# power_board_pcie.net
KiCad netlist of a schematic drawn in EAGLE
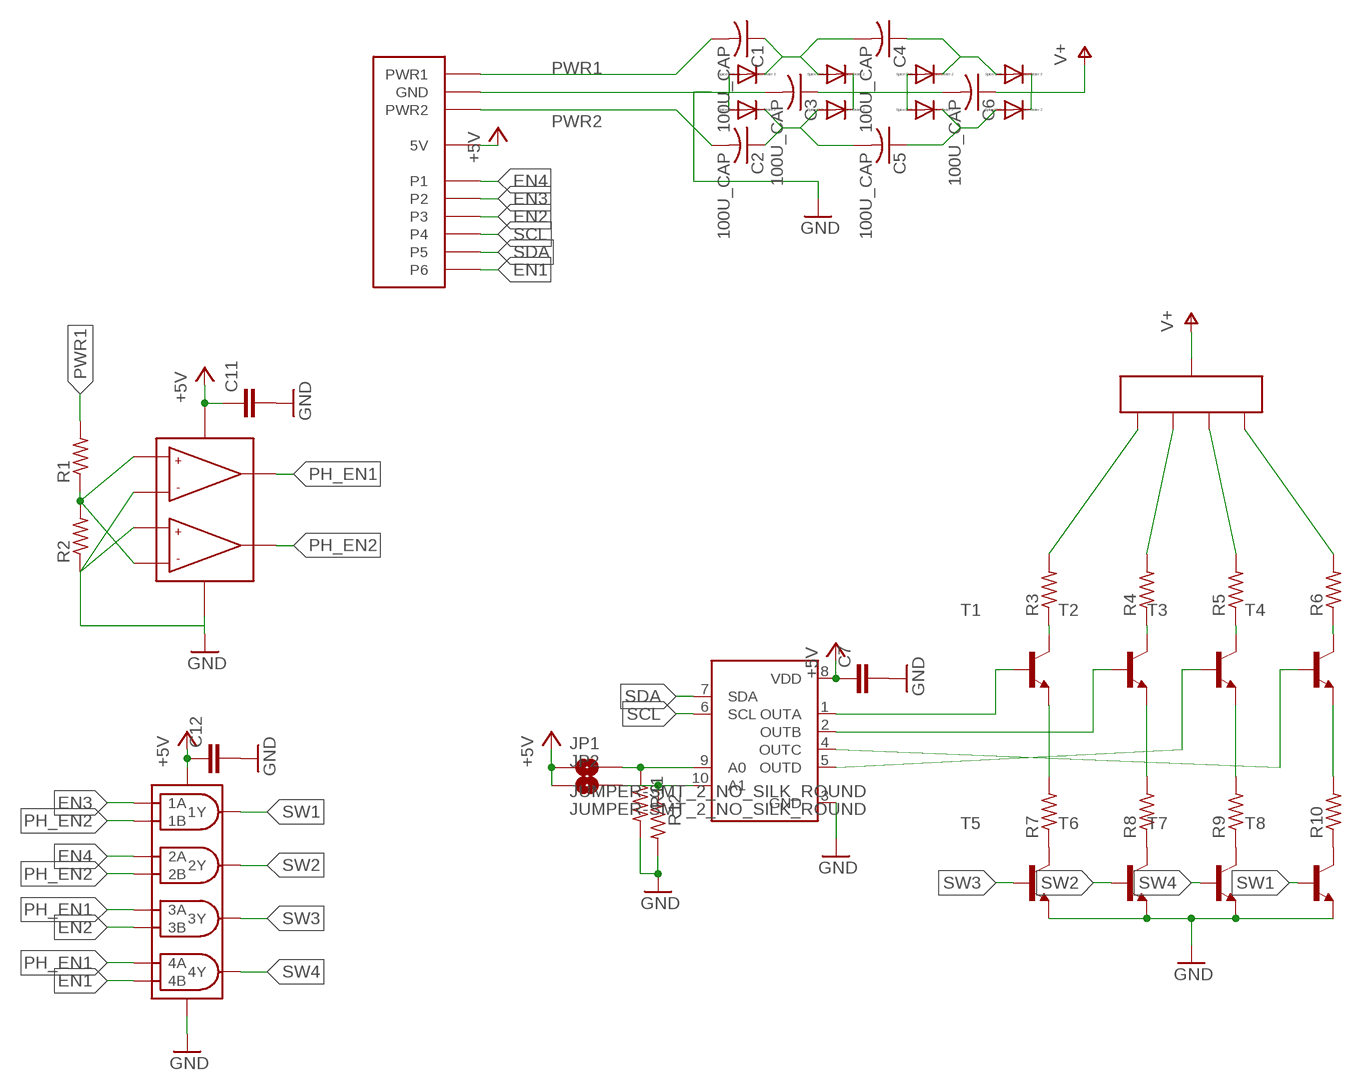
[diagram p0: schematic, sheet 1]

(export (version "E")
  (design (tool "Eeschema 10.0.6"))
  (components
    (comp (ref "C1")
      (value "100U_CAP")
      (footprint "eagle-import:100U_CAP")
      (libsource (lib "eagle-import") (part "100U_CAP"))
    )
    (comp (ref "C2")
      (value "100U_CAP")
      (footprint "eagle-import:100U_CAP")
      (libsource (lib "eagle-import") (part "100U_CAP"))
    )
    (comp (ref "C3")
      (value "100U_CAP")
      (footprint "eagle-import:100U_CAP")
      (libsource (lib "eagle-import") (part "100U_CAP"))
    )
    (comp (ref "C4")
      (value "100U_CAP")
      (footprint "eagle-import:100U_CAP")
      (libsource (lib "eagle-import") (part "100U_CAP"))
    )
    (comp (ref "C5")
      (value "100U_CAP")
      (footprint "eagle-import:100U_CAP")
      (libsource (lib "eagle-import") (part "100U_CAP"))
    )
    (comp (ref "C6")
      (value "100U_CAP")
      (footprint "eagle-import:100U_CAP")
      (libsource (lib "eagle-import") (part "100U_CAP"))
    )
    (comp (ref "C7")
      (value "C-EUC1206")
      (footprint "eagle-import:C1206")
      (libsource (lib "eagle-import") (part "C-EUC1206"))
    )
    (comp (ref "C11")
      (value "C-EUC1206")
      (footprint "eagle-import:C1206")
      (libsource (lib "eagle-import") (part "C-EUC1206"))
    )
    (comp (ref "C12")
      (value "C-EUC1206")
      (footprint "eagle-import:C1206")
      (libsource (lib "eagle-import") (part "C-EUC1206"))
    )
    (comp (ref "D1")
      (value "BAS16GW")
      (footprint "eagle-import:SOD3616X130")
      (libsource (lib "eagle-import") (part "BAS16GW"))
    )
    (comp (ref "D2")
      (value "BAS16GW")
      (footprint "eagle-import:SOD3616X130")
      (libsource (lib "eagle-import") (part "BAS16GW"))
    )
    (comp (ref "D3")
      (value "BAS16GW")
      (footprint "eagle-import:SOD3616X130")
      (libsource (lib "eagle-import") (part "BAS16GW"))
    )
    (comp (ref "D4")
      (value "BAS16GW")
      (footprint "eagle-import:SOD3616X130")
      (libsource (lib "eagle-import") (part "BAS16GW"))
    )
    (comp (ref "D5")
      (value "BAS16GW")
      (footprint "eagle-import:SOD3616X130")
      (libsource (lib "eagle-import") (part "BAS16GW"))
    )
    (comp (ref "D6")
      (value "BAS16GW")
      (footprint "eagle-import:SOD3616X130")
      (libsource (lib "eagle-import") (part "BAS16GW"))
    )
    (comp (ref "D7")
      (value "BAS16GW")
      (footprint "eagle-import:SOD3616X130")
      (libsource (lib "eagle-import") (part "BAS16GW"))
    )
    (comp (ref "D8")
      (value "BAS16GW")
      (footprint "eagle-import:SOD3616X130")
      (libsource (lib "eagle-import") (part "BAS16GW"))
    )
    (comp (ref "J1")
      (value "PCIE_EDGE")
      (footprint "eagle-import:PCIE_EDGE")
      (libsource (lib "eagle-import") (part "PCIE_EDGE"))
    )
    (comp (ref "JP1")
      (value "JUMPER-SMT_2_NO_SILK_ROUND")
      (footprint "eagle-import:SMT-JUMPER_2_NO_SILK_ROUND")
      (libsource (lib "eagle-import") (part "JUMPER-SMT_2_NO_SILK_ROUND"))
    )
    (comp (ref "JP2")
      (value "JUMPER-SMT_2_NO_SILK_ROUND")
      (footprint "eagle-import:SMT-JUMPER_2_NO_SILK_ROUND")
      (libsource (lib "eagle-import") (part "JUMPER-SMT_2_NO_SILK_ROUND"))
    )
    (comp (ref "R1")
      (value "R-US_R1206")
      (footprint "eagle-import:R1206")
      (libsource (lib "eagle-import") (part "R-US_R1206"))
    )
    (comp (ref "R2")
      (value "R-US_R1206")
      (footprint "eagle-import:R1206")
      (libsource (lib "eagle-import") (part "R-US_R1206"))
    )
    (comp (ref "R3")
      (value "R-US_R1206")
      (footprint "eagle-import:R1206")
      (libsource (lib "eagle-import") (part "R-US_R1206"))
    )
    (comp (ref "R4")
      (value "R-US_R1206")
      (footprint "eagle-import:R1206")
      (libsource (lib "eagle-import") (part "R-US_R1206"))
    )
    (comp (ref "R5")
      (value "R-US_R1206")
      (footprint "eagle-import:R1206")
      (libsource (lib "eagle-import") (part "R-US_R1206"))
    )
    (comp (ref "R6")
      (value "R-US_R1206")
      (footprint "eagle-import:R1206")
      (libsource (lib "eagle-import") (part "R-US_R1206"))
    )
    (comp (ref "R7")
      (value "R-US_R1206")
      (footprint "eagle-import:R1206")
      (libsource (lib "eagle-import") (part "R-US_R1206"))
    )
    (comp (ref "R8")
      (value "R-US_R1206")
      (footprint "eagle-import:R1206")
      (libsource (lib "eagle-import") (part "R-US_R1206"))
    )
    (comp (ref "R9")
      (value "R-US_R1206")
      (footprint "eagle-import:R1206")
      (libsource (lib "eagle-import") (part "R-US_R1206"))
    )
    (comp (ref "R10")
      (value "R-US_R1206")
      (footprint "eagle-import:R1206")
      (libsource (lib "eagle-import") (part "R-US_R1206"))
    )
    (comp (ref "R11")
      (value "R-US_R0603")
      (footprint "eagle-import:R0603")
      (libsource (lib "eagle-import") (part "R-US_R0603"))
    )
    (comp (ref "R12")
      (value "R-US_R0603")
      (footprint "eagle-import:R0603")
      (libsource (lib "eagle-import") (part "R-US_R0603"))
    )
    (comp (ref "T1")
      (value "-NPN-SOT23-EBC")
      (footprint "eagle-import:SOT23-EBC")
      (libsource (lib "eagle-import") (part "-NPN-SOT23-EBC"))
    )
    (comp (ref "T2")
      (value "-NPN-SOT23-EBC")
      (footprint "eagle-import:SOT23-EBC")
      (libsource (lib "eagle-import") (part "-NPN-SOT23-EBC"))
    )
    (comp (ref "T3")
      (value "-NPN-SOT23-EBC")
      (footprint "eagle-import:SOT23-EBC")
      (libsource (lib "eagle-import") (part "-NPN-SOT23-EBC"))
    )
    (comp (ref "T4")
      (value "-NPN-SOT23-EBC")
      (footprint "eagle-import:SOT23-EBC")
      (libsource (lib "eagle-import") (part "-NPN-SOT23-EBC"))
    )
    (comp (ref "T5")
      (value "-NPN-SOT23-EBC")
      (footprint "eagle-import:SOT23-EBC")
      (libsource (lib "eagle-import") (part "-NPN-SOT23-EBC"))
    )
    (comp (ref "T6")
      (value "-NPN-SOT23-EBC")
      (footprint "eagle-import:SOT23-EBC")
      (libsource (lib "eagle-import") (part "-NPN-SOT23-EBC"))
    )
    (comp (ref "T7")
      (value "-NPN-SOT23-EBC")
      (footprint "eagle-import:SOT23-EBC")
      (libsource (lib "eagle-import") (part "-NPN-SOT23-EBC"))
    )
    (comp (ref "T8")
      (value "-NPN-SOT23-EBC")
      (footprint "eagle-import:SOT23-EBC")
      (libsource (lib "eagle-import") (part "-NPN-SOT23-EBC"))
    )
    (comp (ref "U$3")
      (value "POWER_EDGE")
      (footprint "eagle-import:POWER_EDGE")
      (libsource (lib "eagle-import") (part "POWER_EDGE"))
    )
    (comp (ref "U1")
      (value "74HCT08D")
      (footprint "eagle-import:SOIC127P600X175-14")
      (libsource (lib "eagle-import") (part "74HCT08D"))
    )
    (comp (ref "U2")
      (value "DAC5574")
      (footprint "eagle-import:SOP50P490X110-10")
      (libsource (lib "eagle-import") (part "DAC5574"))
    )
    (comp (ref "U3")
      (value "AZ4558CMTR-G1")
      (footprint "eagle-import:SOIC127P600X175-8")
      (libsource (lib "eagle-import") (part "AZ4558CMTR-G1"))
    )
  )
  (nets
    (net (code "1") (name "+5V") (class "Default")
      (node (ref "C11") (pin "1") (pinfunction "1_1") (pintype "passive"))
      (node (ref "C12") (pin "1") (pinfunction "1_1") (pintype "passive"))
      (node (ref "C7") (pin "1") (pinfunction "1_1") (pintype "passive"))
      (node (ref "J1") (pin "PWR3") (pinfunction "5V_PWR3") (pintype "passive"))
      (node (ref "J1") (pin "PWR3_2") (pinfunction "5V_PWR3_2") (pintype "passive"))
      (node (ref "JP1") (pin "1") (pinfunction "1_1") (pintype "passive"))
      (node (ref "JP2") (pin "1") (pinfunction "1_1") (pintype "passive"))
      (node (ref "U1") (pin "14") (pinfunction "VCC_14") (pintype "passive"))
      (node (ref "U2") (pin "8") (pinfunction "VDD_8") (pintype "bidirectional"))
      (node (ref "U3") (pin "8") (pinfunction "VCC_8") (pintype "bidirectional"))
    )
    (net (code "2") (name "/PWR2") (class "Default")
      (node (ref "C2") (pin "C") (pinfunction "2_C") (pintype "passive"))
      (node (ref "J1") (pin "P$3") (pinfunction "PWR2_P$3") (pintype "passive"))
      (node (ref "J1") (pin "P$6") (pinfunction "PWR2_P$6") (pintype "passive"))
    )
    (net (code "3") (name "EN1") (class "Default")
      (node (ref "J1") (pin "P6") (pinfunction "P6_P6") (pintype "bidirectional"))
      (node (ref "U1") (pin "13") (pinfunction "4B_13") (pintype "input"))
    )
    (net (code "4") (name "EN2") (class "Default")
      (node (ref "J1") (pin "P3") (pinfunction "P3_P3") (pintype "bidirectional"))
      (node (ref "U1") (pin "10") (pinfunction "3B_10") (pintype "input"))
    )
    (net (code "5") (name "EN3") (class "Default")
      (node (ref "J1") (pin "P2") (pinfunction "P2_P2") (pintype "bidirectional"))
      (node (ref "U1") (pin "1") (pinfunction "1A_1") (pintype "input"))
    )
    (net (code "6") (name "EN4") (class "Default")
      (node (ref "J1") (pin "P1") (pinfunction "P1_P1") (pintype "bidirectional"))
      (node (ref "U1") (pin "4") (pinfunction "2A_4") (pintype "input"))
    )
    (net (code "7") (name "GND") (class "Default")
      (node (ref "C11") (pin "2") (pinfunction "2_2") (pintype "passive"))
      (node (ref "C12") (pin "2") (pinfunction "2_2") (pintype "passive"))
      (node (ref "C3") (pin "C") (pinfunction "2_C") (pintype "passive"))
      (node (ref "C7") (pin "2") (pinfunction "2_2") (pintype "passive"))
      (node (ref "D1") (pin "2") (pinfunction "A_2") (pintype "passive"))
      (node (ref "D2") (pin "2") (pinfunction "A_2") (pintype "passive"))
      (node (ref "J1") (pin "P$2") (pinfunction "GND_P$2") (pintype "passive"))
      (node (ref "J1") (pin "P$5") (pinfunction "GND_P$5") (pintype "passive"))
      (node (ref "R11") (pin "2") (pinfunction "2_2") (pintype "passive"))
      (node (ref "R12") (pin "2") (pinfunction "2_2") (pintype "passive"))
      (node (ref "R2") (pin "1") (pinfunction "1_1") (pintype "passive"))
      (node (ref "T5") (pin "E") (pinfunction "E_E") (pintype "passive"))
      (node (ref "T6") (pin "E") (pinfunction "E_E") (pintype "passive"))
      (node (ref "T7") (pin "E") (pinfunction "E_E") (pintype "passive"))
      (node (ref "T8") (pin "E") (pinfunction "E_E") (pintype "passive"))
      (node (ref "U1") (pin "7") (pinfunction "GND_7") (pintype "passive"))
      (node (ref "U2") (pin "3") (pinfunction "GND_3") (pintype "bidirectional"))
      (node (ref "U3") (pin "2") (pinfunction "IN1-_2") (pintype "input"))
      (node (ref "U3") (pin "4") (pinfunction "VEE_4") (pintype "bidirectional"))
      (node (ref "U3") (pin "5") (pinfunction "IN2+_5") (pintype "input"))
    )
    (net (code "8") (name "Net-(C1-1)") (class "Default")
      (node (ref "C1") (pin "A") (pinfunction "1_A") (pintype "passive"))
      (node (ref "C4") (pin "C") (pinfunction "2_C") (pintype "passive"))
      (node (ref "D1") (pin "1") (pinfunction "C_1") (pintype "passive"))
      (node (ref "D3") (pin "2") (pinfunction "A_2") (pintype "passive"))
    )
    (net (code "9") (name "Net-(C2-1)") (class "Default")
      (node (ref "C2") (pin "A") (pinfunction "1_A") (pintype "passive"))
      (node (ref "C5") (pin "C") (pinfunction "2_C") (pintype "passive"))
      (node (ref "D2") (pin "1") (pinfunction "C_1") (pintype "passive"))
      (node (ref "D4") (pin "2") (pinfunction "A_2") (pintype "passive"))
    )
    (net (code "10") (name "Net-(C3-1)") (class "Default")
      (node (ref "C3") (pin "A") (pinfunction "1_A") (pintype "passive"))
      (node (ref "C6") (pin "C") (pinfunction "2_C") (pintype "passive"))
      (node (ref "D3") (pin "1") (pinfunction "C_1") (pintype "passive"))
      (node (ref "D4") (pin "1") (pinfunction "C_1") (pintype "passive"))
      (node (ref "D5") (pin "2") (pinfunction "A_2") (pintype "passive"))
      (node (ref "D6") (pin "2") (pinfunction "A_2") (pintype "passive"))
    )
    (net (code "11") (name "Net-(C4-1)") (class "Default")
      (node (ref "C4") (pin "A") (pinfunction "1_A") (pintype "passive"))
      (node (ref "D5") (pin "1") (pinfunction "C_1") (pintype "passive"))
      (node (ref "D7") (pin "2") (pinfunction "A_2") (pintype "passive"))
    )
    (net (code "12") (name "Net-(C5-1)") (class "Default")
      (node (ref "C5") (pin "A") (pinfunction "1_A") (pintype "passive"))
      (node (ref "D6") (pin "1") (pinfunction "C_1") (pintype "passive"))
      (node (ref "D8") (pin "2") (pinfunction "A_2") (pintype "passive"))
    )
    (net (code "13") (name "Net-(R3-Pad1)") (class "Default")
      (node (ref "R3") (pin "1") (pinfunction "1_1") (pintype "passive"))
      (node (ref "T1") (pin "C") (pinfunction "C_C") (pintype "passive"))
    )
    (net (code "14") (name "Net-(R3-Pad2)") (class "Default")
      (node (ref "R3") (pin "2") (pinfunction "2_2") (pintype "passive"))
      (node (ref "U$3") (pin "C1") (pinfunction "C1_C1") (pintype "bidirectional"))
    )
    (net (code "15") (name "Net-(R4-Pad1)") (class "Default")
      (node (ref "R4") (pin "1") (pinfunction "1_1") (pintype "passive"))
      (node (ref "T2") (pin "C") (pinfunction "C_C") (pintype "passive"))
    )
    (net (code "16") (name "Net-(R4-Pad2)") (class "Default")
      (node (ref "R4") (pin "2") (pinfunction "2_2") (pintype "passive"))
      (node (ref "U$3") (pin "C2") (pinfunction "C2_C2") (pintype "bidirectional"))
    )
    (net (code "17") (name "Net-(R5-Pad1)") (class "Default")
      (node (ref "R5") (pin "1") (pinfunction "1_1") (pintype "passive"))
      (node (ref "T3") (pin "C") (pinfunction "C_C") (pintype "passive"))
    )
    (net (code "18") (name "Net-(R5-Pad2)") (class "Default")
      (node (ref "R5") (pin "2") (pinfunction "2_2") (pintype "passive"))
      (node (ref "U$3") (pin "C3") (pinfunction "C3_C3") (pintype "bidirectional"))
    )
    (net (code "19") (name "Net-(R6-Pad1)") (class "Default")
      (node (ref "R6") (pin "1") (pinfunction "1_1") (pintype "passive"))
      (node (ref "T4") (pin "C") (pinfunction "C_C") (pintype "passive"))
    )
    (net (code "20") (name "Net-(R6-Pad2)") (class "Default")
      (node (ref "R6") (pin "2") (pinfunction "2_2") (pintype "passive"))
      (node (ref "U$3") (pin "C4") (pinfunction "C4_C4") (pintype "bidirectional"))
    )
    (net (code "21") (name "Net-(R7-Pad1)") (class "Default")
      (node (ref "R7") (pin "1") (pinfunction "1_1") (pintype "passive"))
      (node (ref "T5") (pin "C") (pinfunction "C_C") (pintype "passive"))
    )
    (net (code "22") (name "Net-(R7-Pad2)") (class "Default")
      (node (ref "R7") (pin "2") (pinfunction "2_2") (pintype "passive"))
      (node (ref "T1") (pin "E") (pinfunction "E_E") (pintype "passive"))
    )
    (net (code "23") (name "Net-(R8-Pad1)") (class "Default")
      (node (ref "R8") (pin "1") (pinfunction "1_1") (pintype "passive"))
      (node (ref "T6") (pin "C") (pinfunction "C_C") (pintype "passive"))
    )
    (net (code "24") (name "Net-(R8-Pad2)") (class "Default")
      (node (ref "R8") (pin "2") (pinfunction "2_2") (pintype "passive"))
      (node (ref "T2") (pin "E") (pinfunction "E_E") (pintype "passive"))
    )
    (net (code "25") (name "Net-(R9-Pad1)") (class "Default")
      (node (ref "R9") (pin "1") (pinfunction "1_1") (pintype "passive"))
      (node (ref "T7") (pin "C") (pinfunction "C_C") (pintype "passive"))
    )
    (net (code "26") (name "Net-(R9-Pad2)") (class "Default")
      (node (ref "R9") (pin "2") (pinfunction "2_2") (pintype "passive"))
      (node (ref "T3") (pin "E") (pinfunction "E_E") (pintype "passive"))
    )
    (net (code "27") (name "Net-(R10-Pad1)") (class "Default")
      (node (ref "R10") (pin "1") (pinfunction "1_1") (pintype "passive"))
      (node (ref "T8") (pin "C") (pinfunction "C_C") (pintype "passive"))
    )
    (net (code "28") (name "Net-(R10-Pad2)") (class "Default")
      (node (ref "R10") (pin "2") (pinfunction "2_2") (pintype "passive"))
      (node (ref "T4") (pin "E") (pinfunction "E_E") (pintype "passive"))
    )
    (net (code "29") (name "Net-(U2-A0)") (class "Default")
      (node (ref "JP1") (pin "2") (pinfunction "2_2") (pintype "passive"))
      (node (ref "R11") (pin "1") (pinfunction "1_1") (pintype "passive"))
      (node (ref "U2") (pin "9") (pinfunction "A0_9") (pintype "bidirectional"))
    )
    (net (code "30") (name "Net-(U2-A1)") (class "Default")
      (node (ref "JP2") (pin "2") (pinfunction "2_2") (pintype "passive"))
      (node (ref "R12") (pin "1") (pinfunction "1_1") (pintype "passive"))
      (node (ref "U2") (pin "10") (pinfunction "A1_10") (pintype "bidirectional"))
    )
    (net (code "31") (name "Net-(U2-OUTA)") (class "Default")
      (node (ref "T1") (pin "B") (pinfunction "B_B") (pintype "passive"))
      (node (ref "U2") (pin "1") (pinfunction "OUTA_1") (pintype "bidirectional"))
    )
    (net (code "32") (name "Net-(U2-OUTB)") (class "Default")
      (node (ref "T2") (pin "B") (pinfunction "B_B") (pintype "passive"))
      (node (ref "U2") (pin "2") (pinfunction "OUTB_2") (pintype "bidirectional"))
    )
    (net (code "33") (name "Net-(U2-OUTC)") (class "Default")
      (node (ref "T4") (pin "B") (pinfunction "B_B") (pintype "passive"))
      (node (ref "U2") (pin "4") (pinfunction "OUTC_4") (pintype "bidirectional"))
    )
    (net (code "34") (name "Net-(U2-OUTD)") (class "Default")
      (node (ref "T3") (pin "B") (pinfunction "B_B") (pintype "passive"))
      (node (ref "U2") (pin "5") (pinfunction "OUTD_5") (pintype "bidirectional"))
    )
    (net (code "35") (name "Net-(U3-IN1+)") (class "Default")
      (node (ref "R1") (pin "1") (pinfunction "1_1") (pintype "passive"))
      (node (ref "R2") (pin "2") (pinfunction "2_2") (pintype "passive"))
      (node (ref "U3") (pin "3") (pinfunction "IN1+_3") (pintype "input"))
      (node (ref "U3") (pin "6") (pinfunction "IN2-_6") (pintype "input"))
    )
    (net (code "36") (name "PH_EN1") (class "Default")
      (node (ref "U1") (pin "12") (pinfunction "4A_12") (pintype "input"))
      (node (ref "U1") (pin "9") (pinfunction "3A_9") (pintype "input"))
      (node (ref "U3") (pin "1") (pinfunction "OUT1_1") (pintype "output"))
    )
    (net (code "37") (name "PH_EN2") (class "Default")
      (node (ref "U1") (pin "2") (pinfunction "1B_2") (pintype "input"))
      (node (ref "U1") (pin "5") (pinfunction "2B_5") (pintype "input"))
      (node (ref "U3") (pin "7") (pinfunction "OUT2_7") (pintype "output"))
    )
    (net (code "38") (name "PWR1") (class "Default")
      (node (ref "C1") (pin "C") (pinfunction "2_C") (pintype "passive"))
      (node (ref "J1") (pin "P$1") (pinfunction "PWR1_P$1") (pintype "passive"))
      (node (ref "J1") (pin "P$4") (pinfunction "PWR1_P$4") (pintype "passive"))
      (node (ref "R1") (pin "2") (pinfunction "2_2") (pintype "passive"))
    )
    (net (code "39") (name "SCL") (class "Default")
      (node (ref "J1") (pin "P4") (pinfunction "P4_P4") (pintype "bidirectional"))
      (node (ref "U2") (pin "6") (pinfunction "SCL_6") (pintype "bidirectional"))
    )
    (net (code "40") (name "SDA") (class "Default")
      (node (ref "J1") (pin "P5") (pinfunction "P5_P5") (pintype "bidirectional"))
      (node (ref "U2") (pin "7") (pinfunction "SDA_7") (pintype "bidirectional"))
    )
    (net (code "41") (name "SW1") (class "Default")
      (node (ref "T8") (pin "B") (pinfunction "B_B") (pintype "passive"))
      (node (ref "U1") (pin "3") (pinfunction "1Y_3") (pintype "output"))
    )
    (net (code "42") (name "SW2") (class "Default")
      (node (ref "T6") (pin "B") (pinfunction "B_B") (pintype "passive"))
      (node (ref "U1") (pin "6") (pinfunction "2Y_6") (pintype "output"))
    )
    (net (code "43") (name "SW3") (class "Default")
      (node (ref "T5") (pin "B") (pinfunction "B_B") (pintype "passive"))
      (node (ref "U1") (pin "8") (pinfunction "3Y_8") (pintype "output"))
    )
    (net (code "44") (name "SW4") (class "Default")
      (node (ref "T7") (pin "B") (pinfunction "B_B") (pintype "passive"))
      (node (ref "U1") (pin "11") (pinfunction "4Y_11") (pintype "output"))
    )
    (net (code "45") (name "V+") (class "Default")
      (node (ref "C6") (pin "A") (pinfunction "1_A") (pintype "passive"))
      (node (ref "D7") (pin "1") (pinfunction "C_1") (pintype "passive"))
      (node (ref "D8") (pin "1") (pinfunction "C_1") (pintype "passive"))
      (node (ref "U$3") (pin "A1") (pinfunction "A_A1") (pintype "bidirectional"))
      (node (ref "U$3") (pin "A2") (pinfunction "A_A2") (pintype "bidirectional"))
      (node (ref "U$3") (pin "A3") (pinfunction "A_A3") (pintype "bidirectional"))
      (node (ref "U$3") (pin "A4") (pinfunction "A_A4") (pintype "bidirectional"))
    )
  )
)
